# 7__MOT_CONTROL_LED_STATUS.net
KiCad netlist of a schematic drawn in Altium Designer
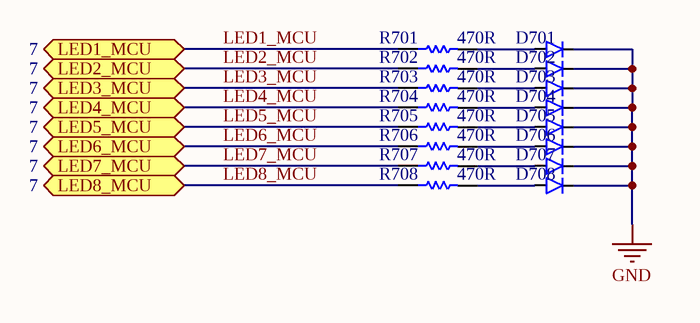
[diagram p0: [7]_MOT_CONTROL LED STATUS.SchDoc]

(export (version "E")
  (design (tool "Eeschema 10.0.6"))
  (components
    (comp (ref "D701") (value "LED 0603") (footprint "LED0603") (libsource (lib "DRIVER") (part "LED 0603")))
    (comp (ref "D702") (value "LED 0603") (footprint "LED0603") (libsource (lib "DRIVER") (part "LED 0603")))
    (comp (ref "D703") (value "LED 0603") (footprint "LED0603") (libsource (lib "DRIVER") (part "LED 0603")))
    (comp (ref "D704") (value "LED 0603") (footprint "LED0603") (libsource (lib "DRIVER") (part "LED 0603")))
    (comp (ref "D705") (value "LED 0603") (footprint "LED0603") (libsource (lib "DRIVER") (part "LED 0603")))
    (comp (ref "D706") (value "LED 0603") (footprint "LED0603") (libsource (lib "DRIVER") (part "LED 0603")))
    (comp (ref "D707") (value "LED 0603") (footprint "LED0603") (libsource (lib "DRIVER") (part "LED 0603")))
    (comp (ref "D708") (value "LED 0603") (footprint "LED0603") (libsource (lib "DRIVER") (part "LED 0603")))
    (comp (ref "R701")
      (value "470R")
      (footprint "res 0603")
      (description "RES SMD, 470 OHM 5% 1/8W 0603")
      (fields
        (field (name "MANUFACTURER1_PART#") "RK73B1JTTD471J")
        (field (name "MANUFACTURER2_PART#") "RMCF0603JT470R")
      )
      (libsource (lib "Full") (part "Res0.3"))
    )
    (comp (ref "R702")
      (value "470R")
      (footprint "res 0603")
      (description "RES SMD, 470 OHM 5% 1/8W 0603")
      (fields
        (field (name "MANUFACTURER1_PART#") "RK73B1JTTD471J")
        (field (name "MANUFACTURER2_PART#") "RMCF0603JT470R")
      )
      (libsource (lib "Full") (part "Res0.3"))
    )
    (comp (ref "R703")
      (value "470R")
      (footprint "res 0603")
      (description "RES SMD, 470 OHM 5% 1/8W 0603")
      (fields
        (field (name "MANUFACTURER1_PART#") "RK73B1JTTD471J")
        (field (name "MANUFACTURER2_PART#") "RMCF0603JT470R")
      )
      (libsource (lib "Full") (part "Res0.3"))
    )
    (comp (ref "R704")
      (value "470R")
      (footprint "res 0603")
      (description "RES SMD, 470 OHM 5% 1/8W 0603")
      (fields
        (field (name "MANUFACTURER1_PART#") "RK73B1JTTD471J")
        (field (name "MANUFACTURER2_PART#") "RMCF0603JT470R")
      )
      (libsource (lib "Full") (part "Res0.3"))
    )
    (comp (ref "R705")
      (value "470R")
      (footprint "res 0603")
      (description "RES SMD, 470 OHM 5% 1/8W 0603")
      (fields
        (field (name "MANUFACTURER1_PART#") "RK73B1JTTD471J")
        (field (name "MANUFACTURER2_PART#") "RMCF0603JT470R")
      )
      (libsource (lib "Full") (part "Res0.3"))
    )
    (comp (ref "R706")
      (value "470R")
      (footprint "res 0603")
      (description "RES SMD, 470 OHM 5% 1/8W 0603")
      (fields
        (field (name "MANUFACTURER1_PART#") "RK73B1JTTD471J")
        (field (name "MANUFACTURER2_PART#") "RMCF0603JT470R")
      )
      (libsource (lib "Full") (part "Res0.3"))
    )
    (comp (ref "R707")
      (value "470R")
      (footprint "res 0603")
      (description "RES SMD, 470 OHM 5% 1/8W 0603")
      (fields
        (field (name "MANUFACTURER1_PART#") "RK73B1JTTD471J")
        (field (name "MANUFACTURER2_PART#") "RMCF0603JT470R")
      )
      (libsource (lib "Full") (part "Res0.3"))
    )
    (comp (ref "R708")
      (value "470R")
      (footprint "res 0603")
      (description "RES SMD, 470 OHM 5% 1/8W 0603")
      (fields
        (field (name "MANUFACTURER1_PART#") "RK73B1JTTD471J")
        (field (name "MANUFACTURER2_PART#") "RMCF0603JT470R")
      )
      (libsource (lib "Full") (part "Res0.3"))
    )
  )
  (nets
    (net (code "1") (name "/LED1_MCU") (class "Default")
      (node (ref "R701") (pin "1") (pinfunction "1_1") (pintype "passive"))
    )
    (net (code "2") (name "/LED2_MCU") (class "Default")
      (node (ref "R702") (pin "1") (pinfunction "1_1") (pintype "passive"))
    )
    (net (code "3") (name "/LED3_MCU") (class "Default")
      (node (ref "R703") (pin "1") (pinfunction "1_1") (pintype "passive"))
    )
    (net (code "4") (name "/LED4_MCU") (class "Default")
      (node (ref "R704") (pin "1") (pinfunction "1_1") (pintype "passive"))
    )
    (net (code "5") (name "/LED5_MCU") (class "Default")
      (node (ref "R705") (pin "1") (pinfunction "1_1") (pintype "passive"))
    )
    (net (code "6") (name "/LED6_MCU") (class "Default")
      (node (ref "R706") (pin "1") (pinfunction "1_1") (pintype "passive"))
    )
    (net (code "7") (name "/LED7_MCU") (class "Default")
      (node (ref "R707") (pin "1") (pinfunction "1_1") (pintype "passive"))
    )
    (net (code "8") (name "/LED8_MCU") (class "Default")
      (node (ref "R708") (pin "1") (pinfunction "1_1") (pintype "passive"))
    )
    (net (code "9") (name "GND") (class "Default")
      (node (ref "D701") (pin "1") (pinfunction "K_1") (pintype "passive"))
      (node (ref "D702") (pin "1") (pinfunction "K_1") (pintype "passive"))
      (node (ref "D703") (pin "1") (pinfunction "K_1") (pintype "passive"))
      (node (ref "D704") (pin "1") (pinfunction "K_1") (pintype "passive"))
      (node (ref "D705") (pin "1") (pinfunction "K_1") (pintype "passive"))
      (node (ref "D706") (pin "1") (pinfunction "K_1") (pintype "passive"))
      (node (ref "D707") (pin "1") (pinfunction "K_1") (pintype "passive"))
      (node (ref "D708") (pin "1") (pinfunction "K_1") (pintype "passive"))
    )
    (net (code "10") (name "Net-(D701-A)") (class "Default")
      (node (ref "D701") (pin "2") (pinfunction "A_2") (pintype "passive"))
      (node (ref "R701") (pin "2") (pinfunction "2_2") (pintype "passive"))
    )
    (net (code "11") (name "Net-(D702-A)") (class "Default")
      (node (ref "D702") (pin "2") (pinfunction "A_2") (pintype "passive"))
      (node (ref "R702") (pin "2") (pinfunction "2_2") (pintype "passive"))
    )
    (net (code "12") (name "Net-(D703-A)") (class "Default")
      (node (ref "D703") (pin "2") (pinfunction "A_2") (pintype "passive"))
      (node (ref "R703") (pin "2") (pinfunction "2_2") (pintype "passive"))
    )
    (net (code "13") (name "Net-(D704-A)") (class "Default")
      (node (ref "D704") (pin "2") (pinfunction "A_2") (pintype "passive"))
      (node (ref "R704") (pin "2") (pinfunction "2_2") (pintype "passive"))
    )
    (net (code "14") (name "Net-(D705-A)") (class "Default")
      (node (ref "D705") (pin "2") (pinfunction "A_2") (pintype "passive"))
      (node (ref "R705") (pin "2") (pinfunction "2_2") (pintype "passive"))
    )
    (net (code "15") (name "Net-(D706-A)") (class "Default")
      (node (ref "D706") (pin "2") (pinfunction "A_2") (pintype "passive"))
      (node (ref "R706") (pin "2") (pinfunction "2_2") (pintype "passive"))
    )
    (net (code "16") (name "Net-(D707-A)") (class "Default")
      (node (ref "D707") (pin "2") (pinfunction "A_2") (pintype "passive"))
      (node (ref "R707") (pin "2") (pinfunction "2_2") (pintype "passive"))
    )
    (net (code "17") (name "Net-(D708-A)") (class "Default")
      (node (ref "D708") (pin "2") (pinfunction "A_2") (pintype "passive"))
      (node (ref "R708") (pin "2") (pinfunction "2_2") (pintype "passive"))
    )
  )
)
